# MC34063HV-02B-SMD.net
KiCad netlist of a schematic drawn in EAGLE
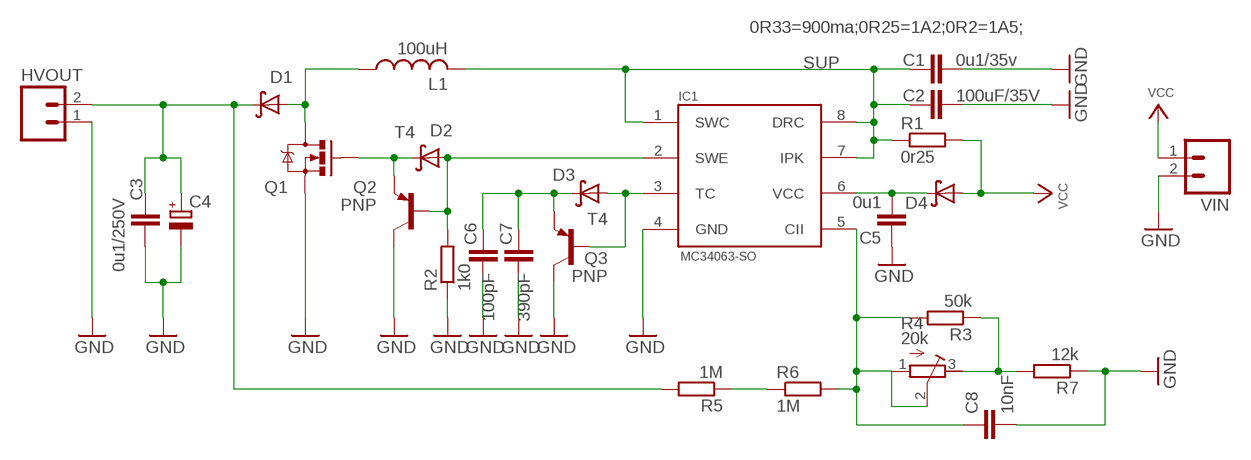
[diagram p0: schematic, sheet 1]

(export (version "E")
  (design (tool "Eeschema 10.0.6"))
  (components
    (comp (ref "C1")
      (value "0u1/35v")
      (footprint "eagle-import:C1206")
      (libsource (lib "eagle-import") (part "C-EUC1206"))
    )
    (comp (ref "C2")
      (value "100uF/35V")
      (footprint "eagle-import:C1206")
      (libsource (lib "eagle-import") (part "C-EUC1206"))
    )
    (comp (ref "C3")
      (value "0u1/250V")
      (footprint "eagle-import:C1206K")
      (libsource (lib "eagle-import") (part "C-EUC1206K"))
    )
    (comp (ref "C4")
      (value "CPOL-EUE5-10.5")
      (footprint "eagle-import:E5-10,5")
      (libsource (lib "eagle-import") (part "CPOL-EUE5-10.5"))
    )
    (comp (ref "C5")
      (value "0u1")
      (footprint "eagle-import:C0603")
      (libsource (lib "eagle-import") (part "C-EUC0603"))
    )
    (comp (ref "C6")
      (value "100pF")
      (footprint "eagle-import:C0603")
      (libsource (lib "eagle-import") (part "C-EUC0603"))
    )
    (comp (ref "C7")
      (value "390pF")
      (footprint "eagle-import:C0603")
      (libsource (lib "eagle-import") (part "C-EUC0603"))
    )
    (comp (ref "C8")
      (value "10nF")
      (footprint "eagle-import:C0603")
      (libsource (lib "eagle-import") (part "C-EUC0603"))
    )
    (comp (ref "D1")
      (value "DIODE-SCHOTTKYSMA")
      (footprint "eagle-import:SMA-DIODE")
      (libsource (lib "eagle-import") (part "DIODE-SCHOTTKYSMA"))
    )
    (comp (ref "D2")
      (value "T4")
      (footprint "eagle-import:SOD123")
      (libsource (lib "eagle-import") (part "DIODE-SCHOTTKYSOD123"))
    )
    (comp (ref "D3")
      (value "T4")
      (footprint "eagle-import:SOD323-W")
      (libsource (lib "eagle-import") (part "DIODE-SCHOTTKYSOD323W"))
    )
    (comp (ref "D4")
      (value "DIODE-SCHOTTKYSMA")
      (footprint "eagle-import:SMA-DIODE")
      (libsource (lib "eagle-import") (part "DIODE-SCHOTTKYSMA"))
    )
    (comp (ref "HVOUT")
      (value "M02PTH")
      (footprint "eagle-import:1X02")
      (libsource (lib "eagle-import") (part "M02PTH"))
    )
    (comp (ref "IC1")
      (value "MC34063-SO")
      (footprint "eagle-import:SO8")
      (libsource (lib "eagle-import") (part "MC34063-SO"))
    )
    (comp (ref "L1")
      (value "100uH")
      (footprint "eagle-import:INDUCTOR11X11")
      (libsource (lib "eagle-import") (part "INDUCTANCE_US11X11PLUG"))
    )
    (comp (ref "Q1")
      (value "MOSFET-NCHANNELTO220V-BH2")
      (footprint "eagle-import:TO220V-BIGHOLE-V2")
      (libsource (lib "eagle-import") (part "MOSFET-NCHANNELTO220V-BH2"))
    )
    (comp (ref "Q2")
      (value "PNP")
      (footprint "eagle-import:SOT23-BEC")
      (libsource (lib "eagle-import") (part "PNP"))
    )
    (comp (ref "Q3")
      (value "PNP")
      (footprint "eagle-import:SOT23-BEC")
      (libsource (lib "eagle-import") (part "PNP"))
    )
    (comp (ref "R1")
      (value "0r25")
      (footprint "eagle-import:R1206")
      (libsource (lib "eagle-import") (part "RESISTOR_EUR1206"))
    )
    (comp (ref "R2")
      (value "1k0")
      (footprint "eagle-import:R0603")
      (libsource (lib "eagle-import") (part "RESISTOR_EUR0603"))
    )
    (comp (ref "R3")
      (value "50k")
      (footprint "eagle-import:R0603")
      (libsource (lib "eagle-import") (part "RESISTOR_EUR0603"))
    )
    (comp (ref "R4")
      (value "20k")
      (footprint "eagle-import:RTRIM3296W")
      (libsource (lib "eagle-import") (part "R-TRIMM3296W"))
    )
    (comp (ref "R5")
      (value "1M")
      (footprint "eagle-import:R1206")
      (libsource (lib "eagle-import") (part "RESISTOR_EUR1206"))
    )
    (comp (ref "R6")
      (value "1M")
      (footprint "eagle-import:R1206")
      (libsource (lib "eagle-import") (part "RESISTOR_EUR1206"))
    )
    (comp (ref "R7")
      (value "12k")
      (footprint "eagle-import:R0603")
      (libsource (lib "eagle-import") (part "RESISTOR_EUR0603"))
    )
    (comp (ref "VIN")
      (value "M02PTH")
      (footprint "eagle-import:1X02")
      (libsource (lib "eagle-import") (part "M02PTH"))
    )
  )
  (nets
    (net (code "1") (name "/SUP") (class "Default")
      (node (ref "C1") (pin "1") (pinfunction "1_1") (pintype "passive"))
      (node (ref "C2") (pin "1") (pinfunction "1_1") (pintype "passive"))
      (node (ref "IC1") (pin "1") (pinfunction "SWC_1") (pintype "bidirectional"))
      (node (ref "IC1") (pin "7") (pinfunction "IPK_7") (pintype "bidirectional"))
      (node (ref "IC1") (pin "8") (pinfunction "DRC_8") (pintype "bidirectional"))
      (node (ref "L1") (pin "P$2") (pinfunction "2_P$2") (pintype "passive"))
      (node (ref "R1") (pin "1") (pinfunction "1_1") (pintype "passive"))
    )
    (net (code "2") (name "GND") (class "Default")
      (node (ref "C1") (pin "2") (pinfunction "2_2") (pintype "passive"))
      (node (ref "C2") (pin "2") (pinfunction "2_2") (pintype "passive"))
      (node (ref "C3") (pin "2") (pinfunction "2_2") (pintype "passive"))
      (node (ref "C4") (pin "-") (pinfunction "-_-") (pintype "passive"))
      (node (ref "C5") (pin "1") (pinfunction "1_1") (pintype "passive"))
      (node (ref "C6") (pin "1") (pinfunction "1_1") (pintype "passive"))
      (node (ref "C7") (pin "1") (pinfunction "1_1") (pintype "passive"))
      (node (ref "C8") (pin "2") (pinfunction "2_2") (pintype "passive"))
      (node (ref "HVOUT") (pin "1") (pinfunction "1_1") (pintype "passive"))
      (node (ref "IC1") (pin "4") (pinfunction "GND_4") (pintype "power_in"))
      (node (ref "Q1") (pin "3") (pinfunction "S_3") (pintype "passive"))
      (node (ref "Q2") (pin "3") (pinfunction "C_3") (pintype "passive"))
      (node (ref "Q3") (pin "3") (pinfunction "C_3") (pintype "passive"))
      (node (ref "R2") (pin "1") (pinfunction "1_1") (pintype "passive"))
      (node (ref "R7") (pin "1") (pinfunction "1_1") (pintype "passive"))
      (node (ref "VIN") (pin "2") (pinfunction "2_2") (pintype "passive"))
    )
    (net (code "3") (name "Net-(C3-Pad1)") (class "Default")
      (node (ref "C3") (pin "1") (pinfunction "1_1") (pintype "passive"))
      (node (ref "C4") (pin "+") (pinfunction "+_+") (pintype "passive"))
      (node (ref "D1") (pin "C") (pinfunction "C_C") (pintype "passive"))
      (node (ref "HVOUT") (pin "2") (pinfunction "2_2") (pintype "passive"))
      (node (ref "R5") (pin "2") (pinfunction "2_2") (pintype "passive"))
    )
    (net (code "4") (name "Net-(IC1-CII)") (class "Default")
      (node (ref "C8") (pin "1") (pinfunction "1_1") (pintype "passive"))
      (node (ref "IC1") (pin "5") (pinfunction "CII_5") (pintype "bidirectional"))
      (node (ref "R3") (pin "2") (pinfunction "2_2") (pintype "passive"))
      (node (ref "R4") (pin "1") (pinfunction "A_1") (pintype "passive"))
      (node (ref "R4") (pin "2") (pinfunction "S_2") (pintype "passive"))
      (node (ref "R6") (pin "2") (pinfunction "2_2") (pintype "passive"))
    )
    (net (code "5") (name "Net-(IC1-SWE)") (class "Default")
      (node (ref "D2") (pin "A") (pinfunction "A_A") (pintype "passive"))
      (node (ref "IC1") (pin "2") (pinfunction "SWE_2") (pintype "bidirectional"))
      (node (ref "Q2") (pin "1") (pinfunction "B_1") (pintype "passive"))
      (node (ref "R2") (pin "2") (pinfunction "2_2") (pintype "passive"))
    )
    (net (code "6") (name "Net-(IC1-TC)") (class "Default")
      (node (ref "D3") (pin "A") (pinfunction "A_A") (pintype "passive"))
      (node (ref "IC1") (pin "3") (pinfunction "TC_3") (pintype "bidirectional"))
      (node (ref "Q3") (pin "1") (pinfunction "B_1") (pintype "passive"))
    )
    (net (code "7") (name "Net-(IC1-VCC)") (class "Default")
      (node (ref "C5") (pin "2") (pinfunction "2_2") (pintype "passive"))
      (node (ref "D4") (pin "C") (pinfunction "C_C") (pintype "passive"))
      (node (ref "IC1") (pin "6") (pinfunction "VCC_6") (pintype "bidirectional"))
    )
    (net (code "8") (name "Net-(L1-1)") (class "Default")
      (node (ref "D1") (pin "A") (pinfunction "A_A") (pintype "passive"))
      (node (ref "L1") (pin "P$1") (pinfunction "1_P$1") (pintype "passive"))
      (node (ref "Q1") (pin "2") (pinfunction "D_2") (pintype "passive"))
    )
    (net (code "9") (name "Net-(Q1-G)") (class "Default")
      (node (ref "D2") (pin "C") (pinfunction "C_C") (pintype "passive"))
      (node (ref "Q1") (pin "1") (pinfunction "G_1") (pintype "passive"))
      (node (ref "Q2") (pin "2") (pinfunction "E_2") (pintype "passive"))
    )
    (net (code "10") (name "Net-(Q3-E)") (class "Default")
      (node (ref "C6") (pin "2") (pinfunction "2_2") (pintype "passive"))
      (node (ref "C7") (pin "2") (pinfunction "2_2") (pintype "passive"))
      (node (ref "D3") (pin "C") (pinfunction "C_C") (pintype "passive"))
      (node (ref "Q3") (pin "2") (pinfunction "E_2") (pintype "passive"))
    )
    (net (code "11") (name "Net-(R4-E)") (class "Default")
      (node (ref "R3") (pin "1") (pinfunction "1_1") (pintype "passive"))
      (node (ref "R4") (pin "3") (pinfunction "E_3") (pintype "passive"))
      (node (ref "R7") (pin "2") (pinfunction "2_2") (pintype "passive"))
    )
    (net (code "12") (name "Net-(R5-Pad1)") (class "Default")
      (node (ref "R5") (pin "1") (pinfunction "1_1") (pintype "passive"))
      (node (ref "R6") (pin "1") (pinfunction "1_1") (pintype "passive"))
    )
    (net (code "13") (name "VCC") (class "Default")
      (node (ref "D4") (pin "A") (pinfunction "A_A") (pintype "passive"))
      (node (ref "R1") (pin "2") (pinfunction "2_2") (pintype "passive"))
      (node (ref "VIN") (pin "1") (pinfunction "1_1") (pintype "passive"))
    )
  )
)
